# 0.net
KiCad netlist of a schematic drawn in EAGLE
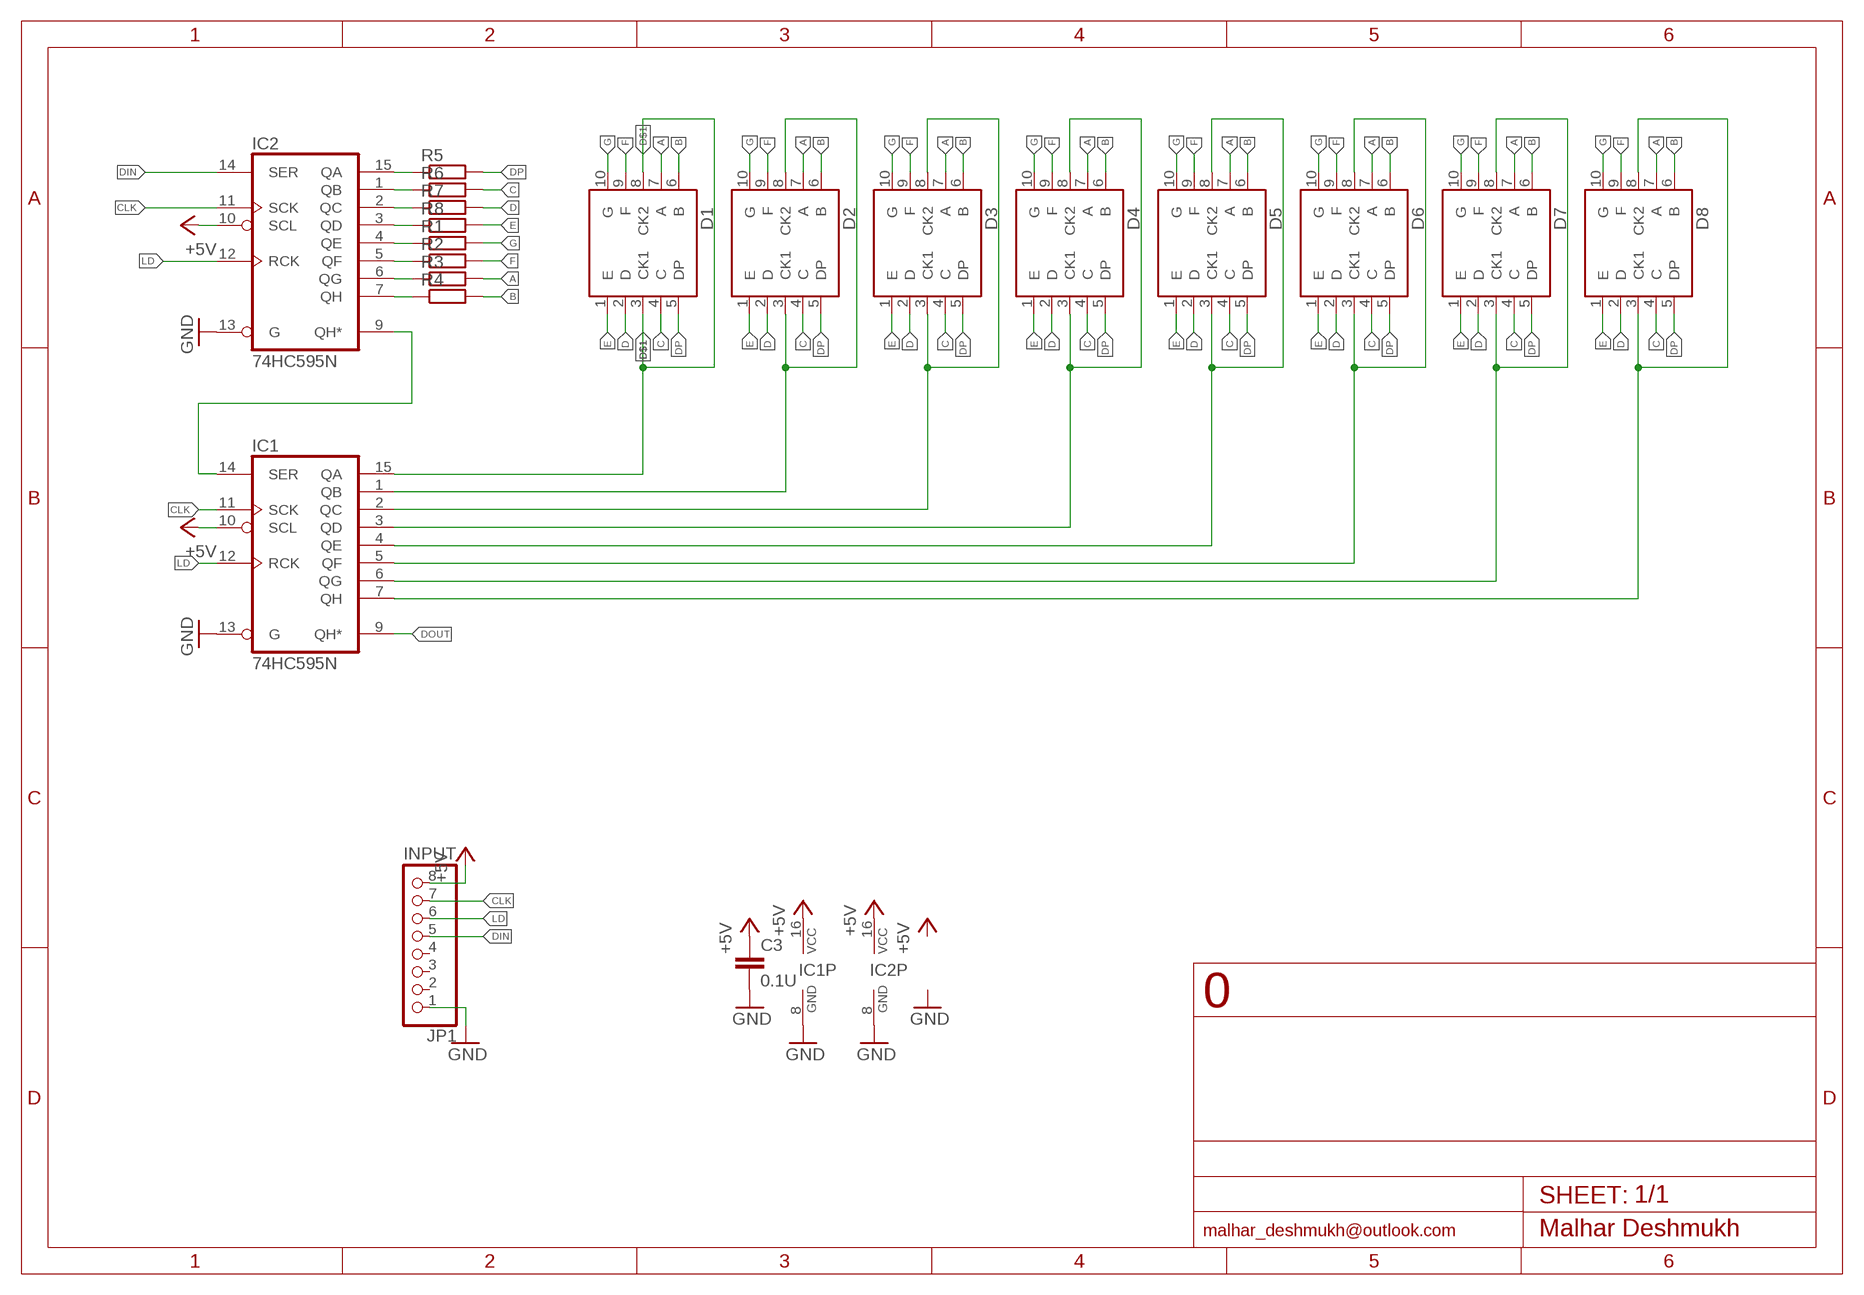
[diagram p0: schematic, sheet 1]

(export (version "E")
  (design (tool "Eeschema 10.0.6"))
  (components
    (comp (ref "C3")
      (value "0.1U")
      (footprint "eagle-import:C050-024X044")
      (libsource (lib "eagle-import") (part "C-EU050-024X044"))
    )
    (comp (ref "D1")
      (value "7SEG-CK")
      (footprint "eagle-import:7SEG-13")
      (libsource (lib "eagle-import") (part "7SEG-CK"))
    )
    (comp (ref "D2")
      (value "7SEG-CK")
      (footprint "eagle-import:7SEG-13")
      (libsource (lib "eagle-import") (part "7SEG-CK"))
    )
    (comp (ref "D3")
      (value "7SEG-CK")
      (footprint "eagle-import:7SEG-13")
      (libsource (lib "eagle-import") (part "7SEG-CK"))
    )
    (comp (ref "D4")
      (value "7SEG-CK")
      (footprint "eagle-import:7SEG-13")
      (libsource (lib "eagle-import") (part "7SEG-CK"))
    )
    (comp (ref "D5")
      (value "7SEG-CK")
      (footprint "eagle-import:7SEG-13")
      (libsource (lib "eagle-import") (part "7SEG-CK"))
    )
    (comp (ref "D6")
      (value "7SEG-CK")
      (footprint "eagle-import:7SEG-13")
      (libsource (lib "eagle-import") (part "7SEG-CK"))
    )
    (comp (ref "D7")
      (value "7SEG-CK")
      (footprint "eagle-import:7SEG-13")
      (libsource (lib "eagle-import") (part "7SEG-CK"))
    )
    (comp (ref "D8")
      (value "7SEG-CK")
      (footprint "eagle-import:7SEG-13")
      (libsource (lib "eagle-import") (part "7SEG-CK"))
    )
    (comp (ref "IC1")
      (value "74HC595N")
      (footprint "eagle-import:DIL16")
      (libsource (lib "eagle-import") (part "74595NHC"))
    )
    (comp (ref "IC2")
      (value "74HC595N")
      (footprint "eagle-import:DIL16")
      (libsource (lib "eagle-import") (part "74595NHC"))
    )
    (comp (ref "JP1")
      (value "INPUT")
      (footprint "eagle-import:1X08")
      (libsource (lib "eagle-import") (part "PINHD-1X8"))
    )
    (comp (ref "R1")
      (value "R-EU_0207/7")
      (footprint "eagle-import:0207_7")
      (libsource (lib "eagle-import") (part "R-EU_0207/7"))
    )
    (comp (ref "R2")
      (value "R-EU_0207/7")
      (footprint "eagle-import:0207_7")
      (libsource (lib "eagle-import") (part "R-EU_0207/7"))
    )
    (comp (ref "R3")
      (value "R-EU_0207/7")
      (footprint "eagle-import:0207_7")
      (libsource (lib "eagle-import") (part "R-EU_0207/7"))
    )
    (comp (ref "R4")
      (value "R-EU_0207/7")
      (footprint "eagle-import:0207_7")
      (libsource (lib "eagle-import") (part "R-EU_0207/7"))
    )
    (comp (ref "R5")
      (value "R-EU_0207/7")
      (footprint "eagle-import:0207_7")
      (libsource (lib "eagle-import") (part "R-EU_0207/7"))
    )
    (comp (ref "R6")
      (value "R-EU_0207/7")
      (footprint "eagle-import:0207_7")
      (libsource (lib "eagle-import") (part "R-EU_0207/7"))
    )
    (comp (ref "R7")
      (value "R-EU_0207/7")
      (footprint "eagle-import:0207_7")
      (libsource (lib "eagle-import") (part "R-EU_0207/7"))
    )
    (comp (ref "R8")
      (value "R-EU_0207/7")
      (footprint "eagle-import:0207_7")
      (libsource (lib "eagle-import") (part "R-EU_0207/7"))
    )
  )
  (nets
    (net (code "1") (name "+5V") (class "Default")
      (node (ref "C3") (pin "1") (pinfunction "1_1") (pintype "passive"))
      (node (ref "IC1") (pin "10") (pinfunction "SCL_10") (pintype "input"))
      (node (ref "IC1") (pin "16") (pinfunction "VCC_16") (pintype "power_in"))
      (node (ref "IC2") (pin "10") (pinfunction "SCL_10") (pintype "input"))
      (node (ref "IC2") (pin "16") (pinfunction "VCC_16") (pintype "power_in"))
      (node (ref "JP1") (pin "8") (pinfunction "8_8") (pintype "passive"))
    )
    (net (code "2") (name "A") (class "Default")
      (node (ref "D1") (pin "7") (pinfunction "A_7") (pintype "passive"))
      (node (ref "D2") (pin "7") (pinfunction "A_7") (pintype "passive"))
      (node (ref "D3") (pin "7") (pinfunction "A_7") (pintype "passive"))
      (node (ref "D4") (pin "7") (pinfunction "A_7") (pintype "passive"))
      (node (ref "D5") (pin "7") (pinfunction "A_7") (pintype "passive"))
      (node (ref "D6") (pin "7") (pinfunction "A_7") (pintype "passive"))
      (node (ref "D7") (pin "7") (pinfunction "A_7") (pintype "passive"))
      (node (ref "D8") (pin "7") (pinfunction "A_7") (pintype "passive"))
      (node (ref "R3") (pin "2") (pinfunction "2_2") (pintype "passive"))
    )
    (net (code "3") (name "B") (class "Default")
      (node (ref "D1") (pin "6") (pinfunction "B_6") (pintype "passive"))
      (node (ref "D2") (pin "6") (pinfunction "B_6") (pintype "passive"))
      (node (ref "D3") (pin "6") (pinfunction "B_6") (pintype "passive"))
      (node (ref "D4") (pin "6") (pinfunction "B_6") (pintype "passive"))
      (node (ref "D5") (pin "6") (pinfunction "B_6") (pintype "passive"))
      (node (ref "D6") (pin "6") (pinfunction "B_6") (pintype "passive"))
      (node (ref "D7") (pin "6") (pinfunction "B_6") (pintype "passive"))
      (node (ref "D8") (pin "6") (pinfunction "B_6") (pintype "passive"))
      (node (ref "R4") (pin "2") (pinfunction "2_2") (pintype "passive"))
    )
    (net (code "4") (name "C") (class "Default")
      (node (ref "D1") (pin "4") (pinfunction "C_4") (pintype "passive"))
      (node (ref "D2") (pin "4") (pinfunction "C_4") (pintype "passive"))
      (node (ref "D3") (pin "4") (pinfunction "C_4") (pintype "passive"))
      (node (ref "D4") (pin "4") (pinfunction "C_4") (pintype "passive"))
      (node (ref "D5") (pin "4") (pinfunction "C_4") (pintype "passive"))
      (node (ref "D6") (pin "4") (pinfunction "C_4") (pintype "passive"))
      (node (ref "D7") (pin "4") (pinfunction "C_4") (pintype "passive"))
      (node (ref "D8") (pin "4") (pinfunction "C_4") (pintype "passive"))
      (node (ref "R6") (pin "2") (pinfunction "2_2") (pintype "passive"))
    )
    (net (code "5") (name "CLK") (class "Default")
      (node (ref "IC1") (pin "11") (pinfunction "SCK_11") (pintype "input"))
      (node (ref "IC2") (pin "11") (pinfunction "SCK_11") (pintype "input"))
      (node (ref "JP1") (pin "7") (pinfunction "7_7") (pintype "passive"))
    )
    (net (code "6") (name "D") (class "Default")
      (node (ref "D1") (pin "2") (pinfunction "D_2") (pintype "passive"))
      (node (ref "D2") (pin "2") (pinfunction "D_2") (pintype "passive"))
      (node (ref "D3") (pin "2") (pinfunction "D_2") (pintype "passive"))
      (node (ref "D4") (pin "2") (pinfunction "D_2") (pintype "passive"))
      (node (ref "D5") (pin "2") (pinfunction "D_2") (pintype "passive"))
      (node (ref "D6") (pin "2") (pinfunction "D_2") (pintype "passive"))
      (node (ref "D7") (pin "2") (pinfunction "D_2") (pintype "passive"))
      (node (ref "D8") (pin "2") (pinfunction "D_2") (pintype "passive"))
      (node (ref "R7") (pin "2") (pinfunction "2_2") (pintype "passive"))
    )
    (net (code "7") (name "D$1") (class "Default")
      (node (ref "D1") (pin "3") (pinfunction "CK1_3") (pintype "passive"))
      (node (ref "D1") (pin "8") (pinfunction "CK2_8") (pintype "passive"))
      (node (ref "IC1") (pin "15") (pinfunction "QA_15") (pintype "tri_state"))
    )
    (net (code "8") (name "DIN") (class "Default")
      (node (ref "IC2") (pin "14") (pinfunction "SER_14") (pintype "input"))
      (node (ref "JP1") (pin "5") (pinfunction "5_5") (pintype "passive"))
    )
    (net (code "9") (name "DOUT") (class "Default")
      (node (ref "IC1") (pin "9") (pinfunction "QH*_9") (pintype "tri_state"))
    )
    (net (code "10") (name "DP") (class "Default")
      (node (ref "D1") (pin "5") (pinfunction "DP_5") (pintype "passive"))
      (node (ref "D2") (pin "5") (pinfunction "DP_5") (pintype "passive"))
      (node (ref "D3") (pin "5") (pinfunction "DP_5") (pintype "passive"))
      (node (ref "D4") (pin "5") (pinfunction "DP_5") (pintype "passive"))
      (node (ref "D5") (pin "5") (pinfunction "DP_5") (pintype "passive"))
      (node (ref "D6") (pin "5") (pinfunction "DP_5") (pintype "passive"))
      (node (ref "D7") (pin "5") (pinfunction "DP_5") (pintype "passive"))
      (node (ref "D8") (pin "5") (pinfunction "DP_5") (pintype "passive"))
      (node (ref "R5") (pin "2") (pinfunction "2_2") (pintype "passive"))
    )
    (net (code "11") (name "E") (class "Default")
      (node (ref "D1") (pin "1") (pinfunction "E_1") (pintype "passive"))
      (node (ref "D2") (pin "1") (pinfunction "E_1") (pintype "passive"))
      (node (ref "D3") (pin "1") (pinfunction "E_1") (pintype "passive"))
      (node (ref "D4") (pin "1") (pinfunction "E_1") (pintype "passive"))
      (node (ref "D5") (pin "1") (pinfunction "E_1") (pintype "passive"))
      (node (ref "D6") (pin "1") (pinfunction "E_1") (pintype "passive"))
      (node (ref "D7") (pin "1") (pinfunction "E_1") (pintype "passive"))
      (node (ref "D8") (pin "1") (pinfunction "E_1") (pintype "passive"))
      (node (ref "R8") (pin "2") (pinfunction "2_2") (pintype "passive"))
    )
    (net (code "12") (name "F") (class "Default")
      (node (ref "D1") (pin "9") (pinfunction "F_9") (pintype "passive"))
      (node (ref "D2") (pin "9") (pinfunction "F_9") (pintype "passive"))
      (node (ref "D3") (pin "9") (pinfunction "F_9") (pintype "passive"))
      (node (ref "D4") (pin "9") (pinfunction "F_9") (pintype "passive"))
      (node (ref "D5") (pin "9") (pinfunction "F_9") (pintype "passive"))
      (node (ref "D6") (pin "9") (pinfunction "F_9") (pintype "passive"))
      (node (ref "D7") (pin "9") (pinfunction "F_9") (pintype "passive"))
      (node (ref "D8") (pin "9") (pinfunction "F_9") (pintype "passive"))
      (node (ref "R2") (pin "2") (pinfunction "2_2") (pintype "passive"))
    )
    (net (code "13") (name "G") (class "Default")
      (node (ref "D1") (pin "10") (pinfunction "G_10") (pintype "passive"))
      (node (ref "D2") (pin "10") (pinfunction "G_10") (pintype "passive"))
      (node (ref "D3") (pin "10") (pinfunction "G_10") (pintype "passive"))
      (node (ref "D4") (pin "10") (pinfunction "G_10") (pintype "passive"))
      (node (ref "D5") (pin "10") (pinfunction "G_10") (pintype "passive"))
      (node (ref "D6") (pin "10") (pinfunction "G_10") (pintype "passive"))
      (node (ref "D7") (pin "10") (pinfunction "G_10") (pintype "passive"))
      (node (ref "D8") (pin "10") (pinfunction "G_10") (pintype "passive"))
      (node (ref "R1") (pin "2") (pinfunction "2_2") (pintype "passive"))
    )
    (net (code "14") (name "GND") (class "Default")
      (node (ref "C3") (pin "2") (pinfunction "2_2") (pintype "passive"))
      (node (ref "IC1") (pin "13") (pinfunction "G_13") (pintype "input"))
      (node (ref "IC1") (pin "8") (pinfunction "GND_8") (pintype "power_in"))
      (node (ref "IC2") (pin "13") (pinfunction "G_13") (pintype "input"))
      (node (ref "IC2") (pin "8") (pinfunction "GND_8") (pintype "power_in"))
      (node (ref "JP1") (pin "1") (pinfunction "1_1") (pintype "passive"))
    )
    (net (code "15") (name "LD") (class "Default")
      (node (ref "IC1") (pin "12") (pinfunction "RCK_12") (pintype "input"))
      (node (ref "IC2") (pin "12") (pinfunction "RCK_12") (pintype "input"))
      (node (ref "JP1") (pin "6") (pinfunction "6_6") (pintype "passive"))
    )
    (net (code "16") (name "Net-(D2-CK1)") (class "Default")
      (node (ref "D2") (pin "3") (pinfunction "CK1_3") (pintype "passive"))
      (node (ref "D2") (pin "8") (pinfunction "CK2_8") (pintype "passive"))
      (node (ref "IC1") (pin "1") (pinfunction "QB_1") (pintype "tri_state"))
    )
    (net (code "17") (name "Net-(D3-CK1)") (class "Default")
      (node (ref "D3") (pin "3") (pinfunction "CK1_3") (pintype "passive"))
      (node (ref "D3") (pin "8") (pinfunction "CK2_8") (pintype "passive"))
      (node (ref "IC1") (pin "2") (pinfunction "QC_2") (pintype "tri_state"))
    )
    (net (code "18") (name "Net-(D4-CK1)") (class "Default")
      (node (ref "D4") (pin "3") (pinfunction "CK1_3") (pintype "passive"))
      (node (ref "D4") (pin "8") (pinfunction "CK2_8") (pintype "passive"))
      (node (ref "IC1") (pin "3") (pinfunction "QD_3") (pintype "tri_state"))
    )
    (net (code "19") (name "Net-(D5-CK1)") (class "Default")
      (node (ref "D5") (pin "3") (pinfunction "CK1_3") (pintype "passive"))
      (node (ref "D5") (pin "8") (pinfunction "CK2_8") (pintype "passive"))
      (node (ref "IC1") (pin "4") (pinfunction "QE_4") (pintype "tri_state"))
    )
    (net (code "20") (name "Net-(D6-CK1)") (class "Default")
      (node (ref "D6") (pin "3") (pinfunction "CK1_3") (pintype "passive"))
      (node (ref "D6") (pin "8") (pinfunction "CK2_8") (pintype "passive"))
      (node (ref "IC1") (pin "5") (pinfunction "QF_5") (pintype "tri_state"))
    )
    (net (code "21") (name "Net-(D7-CK1)") (class "Default")
      (node (ref "D7") (pin "3") (pinfunction "CK1_3") (pintype "passive"))
      (node (ref "D7") (pin "8") (pinfunction "CK2_8") (pintype "passive"))
      (node (ref "IC1") (pin "6") (pinfunction "QG_6") (pintype "tri_state"))
    )
    (net (code "22") (name "Net-(D8-CK1)") (class "Default")
      (node (ref "D8") (pin "3") (pinfunction "CK1_3") (pintype "passive"))
      (node (ref "D8") (pin "8") (pinfunction "CK2_8") (pintype "passive"))
      (node (ref "IC1") (pin "7") (pinfunction "QH_7") (pintype "tri_state"))
    )
    (net (code "23") (name "Net-(IC1A-SER)") (class "Default")
      (node (ref "IC1") (pin "14") (pinfunction "SER_14") (pintype "input"))
      (node (ref "IC2") (pin "9") (pinfunction "QH*_9") (pintype "tri_state"))
    )
    (net (code "24") (name "Net-(IC2A-QA)") (class "Default")
      (node (ref "IC2") (pin "15") (pinfunction "QA_15") (pintype "tri_state"))
      (node (ref "R5") (pin "1") (pinfunction "1_1") (pintype "passive"))
    )
    (net (code "25") (name "Net-(IC2A-QB)") (class "Default")
      (node (ref "IC2") (pin "1") (pinfunction "QB_1") (pintype "tri_state"))
      (node (ref "R6") (pin "1") (pinfunction "1_1") (pintype "passive"))
    )
    (net (code "26") (name "Net-(IC2A-QC)") (class "Default")
      (node (ref "IC2") (pin "2") (pinfunction "QC_2") (pintype "tri_state"))
      (node (ref "R7") (pin "1") (pinfunction "1_1") (pintype "passive"))
    )
    (net (code "27") (name "Net-(IC2A-QD)") (class "Default")
      (node (ref "IC2") (pin "3") (pinfunction "QD_3") (pintype "tri_state"))
      (node (ref "R8") (pin "1") (pinfunction "1_1") (pintype "passive"))
    )
    (net (code "28") (name "Net-(IC2A-QE)") (class "Default")
      (node (ref "IC2") (pin "4") (pinfunction "QE_4") (pintype "tri_state"))
      (node (ref "R1") (pin "1") (pinfunction "1_1") (pintype "passive"))
    )
    (net (code "29") (name "Net-(IC2A-QF)") (class "Default")
      (node (ref "IC2") (pin "5") (pinfunction "QF_5") (pintype "tri_state"))
      (node (ref "R2") (pin "1") (pinfunction "1_1") (pintype "passive"))
    )
    (net (code "30") (name "Net-(IC2A-QG)") (class "Default")
      (node (ref "IC2") (pin "6") (pinfunction "QG_6") (pintype "tri_state"))
      (node (ref "R3") (pin "1") (pinfunction "1_1") (pintype "passive"))
    )
    (net (code "31") (name "Net-(IC2A-QH)") (class "Default")
      (node (ref "IC2") (pin "7") (pinfunction "QH_7") (pintype "tri_state"))
      (node (ref "R4") (pin "1") (pinfunction "1_1") (pintype "passive"))
    )
    (net (code "32") (name "unconnected-(JP1-Pad2)") (class "Default")
      (node (ref "JP1") (pin "2") (pinfunction "2_2") (pintype "passive"))
    )
    (net (code "33") (name "unconnected-(JP1-Pad3)") (class "Default")
      (node (ref "JP1") (pin "3") (pinfunction "3_3") (pintype "passive"))
    )
    (net (code "34") (name "unconnected-(JP1-Pad4)") (class "Default")
      (node (ref "JP1") (pin "4") (pinfunction "4_4") (pintype "passive"))
    )
  )
)
